# Wifi.net
KiCad netlist of a schematic drawn in Altium Designer
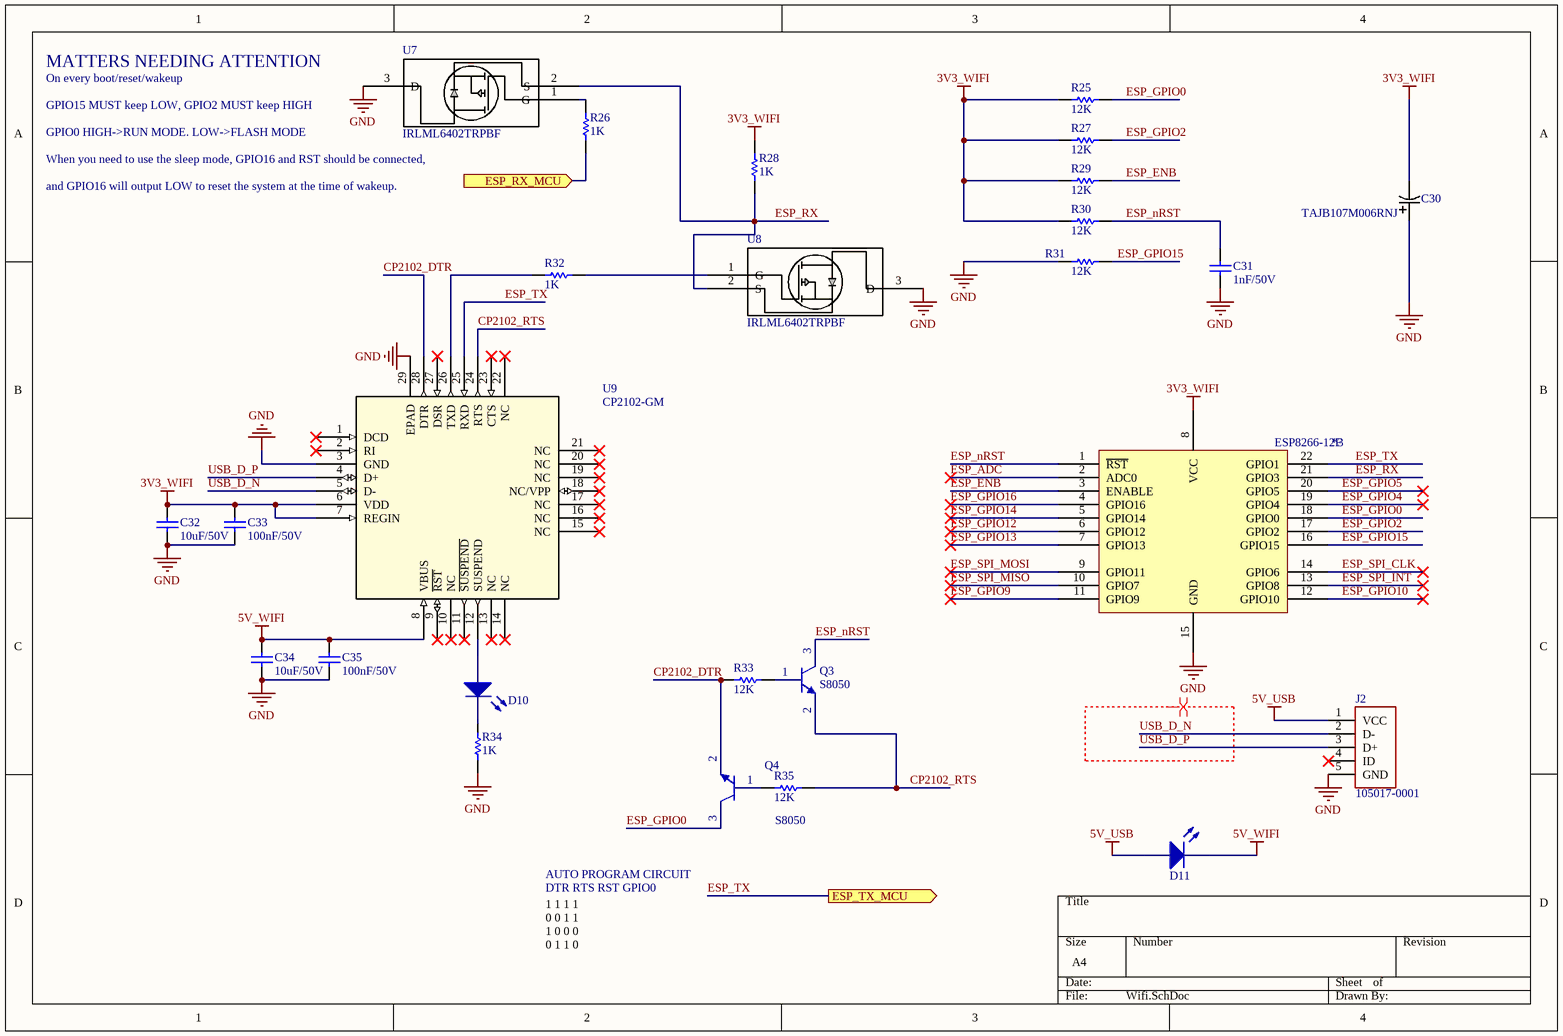
[diagram p0: Wifi.SchDoc]

(export (version "E")
  (design (tool "Eeschema 10.0.6"))
  (components
    (comp (ref "*3")
      (value "ESP8266-12F")
      (footprint "ESP8266")
      (libsource (lib "Schlib1") (part "ESP8266-12F"))
    )
    (comp (ref "C30")
      (value "TAJB107M006RNJ")
      (footprint "TAJB107M006RNJ")
      (fields (field (name "COPYRIGHT") "Copyright (C) 2018 Accelerated Designs. All rights reserved"))
      (libsource (lib "Integrated_Library") (part "TAJB107M006RNJ"))
    )
    (comp (ref "C31")
      (value "1nF/50V")
      (footprint "CAP-SM-0805")
      (description "CAP CER 1000PF 100V X7R 0805")
      (fields
        (field (name "MANUFACTURER") "Johanson Dielectrics Inc.")
        (field (name "MANUFACTURER PART NUMBER") "101X15W102MV4E")
      )
      (libsource (lib "Capacitor") (part "Cap-1nF-50V-0805"))
    )
    (comp (ref "C32")
      (value "10uF/50V")
      (footprint "CAP-SM-0805")
      (description "CAP CER 1000PF 100V X7R 0805")
      (fields
        (field (name "MANUFACTURER") "Johanson Dielectrics Inc.")
        (field (name "MANUFACTURER PART NUMBER") "101X15W102MV4E")
      )
      (libsource (lib "Capacitor") (part "Cap-1nF-50V-0805"))
    )
    (comp (ref "C33")
      (value "100nF/50V")
      (footprint "CAP-SM-0805")
      (description "CAP CER 1000PF 100V X7R 0805")
      (fields
        (field (name "MANUFACTURER") "Johanson Dielectrics Inc.")
        (field (name "MANUFACTURER PART NUMBER") "101X15W102MV4E")
      )
      (libsource (lib "Capacitor") (part "Cap-1nF-50V-0805"))
    )
    (comp (ref "C34")
      (value "10uF/50V")
      (footprint "CAP-SM-0805")
      (description "CAP CER 1000PF 100V X7R 0805")
      (fields
        (field (name "MANUFACTURER") "Johanson Dielectrics Inc.")
        (field (name "MANUFACTURER PART NUMBER") "101X15W102MV4E")
      )
      (libsource (lib "Capacitor") (part "Cap-1nF-50V-0805"))
    )
    (comp (ref "C35")
      (value "100nF/50V")
      (footprint "CAP-SM-0805")
      (description "CAP CER 1000PF 100V X7R 0805")
      (fields
        (field (name "MANUFACTURER") "Johanson Dielectrics Inc.")
        (field (name "MANUFACTURER PART NUMBER") "101X15W102MV4E")
      )
      (libsource (lib "Capacitor") (part "Cap-1nF-50V-0805"))
    )
    (comp (ref "D10") (value "LED") (footprint "LED_0603_Blue") (libsource (lib "PIF_C16_lib") (part "LED")))
    (comp (ref "D11") (value "LED") (footprint "LED_0603_Blue") (libsource (lib "PIF_C16_lib") (part "LED")))
    (comp (ref "J2")
      (value "105017-0001")
      (footprint "CONN_105017-0001")
      (description "No Description Available")
      (fields (field (name "COPYRIGHT") "Copyright (C) 2018 Accelerated Designs. All rights reserved"))
      (libsource (lib "Header-connector") (part "105017-0001"))
    )
    (comp (ref "Q3") (value "S8050") (footprint "SOT23_NEX") (libsource (lib "BJT") (part "S8050")))
    (comp (ref "Q4") (value "S8050") (footprint "SOT23_NEX") (libsource (lib "BJT") (part "S8050")))
    (comp (ref "R25")
      (value "12K")
      (footprint "Resistor:RES-SM-0805")
      (description "RES 0 OHM JUMPER 0805")
      (fields
        (field (name "MANUFACTURER") "Vishay Dale")
        (field (name "MANUFACTURER PART NUMBER") "WSL080500000ZEA9")
      )
      (libsource (lib "Resistor") (part "Res-0-0805"))
    )
    (comp (ref "R26")
      (value "1K")
      (footprint "Resistor:RES-SM-0805")
      (description "RES 470 OHM JUMPER 0805")
      (fields
        (field (name "MANUFACTURER") "YAG6006CT-ND")
        (field (name "MANUFACTURER PART NUMBER") "PE0805FRF7W0R047L")
      )
      (libsource (lib "Resistor") (part "Res-470-0805"))
    )
    (comp (ref "R27")
      (value "12K")
      (footprint "Resistor:RES-SM-0805")
      (description "RES 0 OHM JUMPER 0805")
      (fields
        (field (name "MANUFACTURER") "Vishay Dale")
        (field (name "MANUFACTURER PART NUMBER") "WSL080500000ZEA9")
      )
      (libsource (lib "Resistor") (part "Res-0-0805"))
    )
    (comp (ref "R28")
      (value "1K")
      (footprint "Resistor:RES-SM-0805")
      (description "RES 470 OHM JUMPER 0805")
      (fields
        (field (name "MANUFACTURER") "YAG6006CT-ND")
        (field (name "MANUFACTURER PART NUMBER") "PE0805FRF7W0R047L")
      )
      (libsource (lib "Resistor") (part "Res-470-0805"))
    )
    (comp (ref "R29")
      (value "12K")
      (footprint "Resistor:RES-SM-0805")
      (description "RES 0 OHM JUMPER 0805")
      (fields
        (field (name "MANUFACTURER") "Vishay Dale")
        (field (name "MANUFACTURER PART NUMBER") "WSL080500000ZEA9")
      )
      (libsource (lib "Resistor") (part "Res-0-0805"))
    )
    (comp (ref "R30")
      (value "12K")
      (footprint "Resistor:RES-SM-0805")
      (description "RES 0 OHM JUMPER 0805")
      (fields
        (field (name "MANUFACTURER") "Vishay Dale")
        (field (name "MANUFACTURER PART NUMBER") "WSL080500000ZEA9")
      )
      (libsource (lib "Resistor") (part "Res-0-0805"))
    )
    (comp (ref "R31")
      (value "12K")
      (footprint "Resistor:RES-SM-0805")
      (description "RES 0 OHM JUMPER 0805")
      (fields
        (field (name "MANUFACTURER") "Vishay Dale")
        (field (name "MANUFACTURER PART NUMBER") "WSL080500000ZEA9")
      )
      (libsource (lib "Resistor") (part "Res-0-0805"))
    )
    (comp (ref "R32")
      (value "1K")
      (footprint "Resistor:RES-SM-0805")
      (description "RES 470 OHM JUMPER 0805")
      (fields
        (field (name "MANUFACTURER") "YAG6006CT-ND")
        (field (name "MANUFACTURER PART NUMBER") "PE0805FRF7W0R047L")
      )
      (libsource (lib "Resistor") (part "Res-470-0805"))
    )
    (comp (ref "R33")
      (value "12K")
      (footprint "Resistor:RES-SM-0805")
      (description "RES 0 OHM JUMPER 0805")
      (fields
        (field (name "MANUFACTURER") "Vishay Dale")
        (field (name "MANUFACTURER PART NUMBER") "WSL080500000ZEA9")
      )
      (libsource (lib "Resistor") (part "Res-0-0805"))
    )
    (comp (ref "R34")
      (value "1K")
      (footprint "Resistor:RES-SM-0805")
      (description "RES 470 OHM JUMPER 0805")
      (fields
        (field (name "MANUFACTURER") "YAG6006CT-ND")
        (field (name "MANUFACTURER PART NUMBER") "PE0805FRF7W0R047L")
      )
      (libsource (lib "Resistor") (part "Res-470-0805"))
    )
    (comp (ref "R35")
      (value "12K")
      (footprint "Resistor:RES-SM-0805")
      (description "RES 0 OHM JUMPER 0805")
      (fields
        (field (name "MANUFACTURER") "Vishay Dale")
        (field (name "MANUFACTURER PART NUMBER") "WSL080500000ZEA9")
      )
      (libsource (lib "Resistor") (part "Res-0-0805"))
    )
    (comp (ref "U7")
      (value "IRLML6402TRPBF")
      (footprint "IRLML6402TRPBF")
      (description "No Description Available")
      (fields (field (name "COPYRIGHT") "Copyright (C) 2018 Accelerated Designs. All rights reserved"))
      (libsource (lib "Integrated_Library") (part "IRLML6402TRPBF"))
    )
    (comp (ref "U8")
      (value "IRLML6402TRPBF")
      (footprint "IRLML6402TRPBF")
      (description "No Description Available")
      (fields (field (name "COPYRIGHT") "Copyright (C) 2018 Accelerated Designs. All rights reserved"))
      (libsource (lib "Integrated_Library") (part "IRLML6402TRPBF"))
    )
    (comp (ref "U9")
      (value "CP2102-GM")
      (footprint "cp2102-gm")
      (fields (field (name "COPYRIGHT") "Copyright (C) 2018 Accelerated Designs. All rights reserved"))
      (libsource (lib "Schlib1") (part "CP2102-GM"))
    )
  )
  (nets
    (net (code "1") (name "/CP2102_DTR") (class "Default")
      (node (ref "Q4") (pin "2") (pinfunction "E_2") (pintype "passive"))
      (node (ref "R33") (pin "1") (pinfunction "1_1") (pintype "passive"))
      (node (ref "U9") (pin "28") (pinfunction "DTR_28") (pintype "output"))
    )
    (net (code "2") (name "/CP2102_RTS") (class "Default")
      (node (ref "Q3") (pin "2") (pinfunction "E_2") (pintype "passive"))
      (node (ref "R35") (pin "2") (pinfunction "2_2") (pintype "passive"))
      (node (ref "U9") (pin "24") (pinfunction "RTS_24") (pintype "output"))
    )
    (net (code "3") (name "/ESP_ADC") (class "Default")
      (node (ref "*3") (pin "2") (pinfunction "ADC0_2") (pintype "passive+no_connect"))
    )
    (net (code "4") (name "/ESP_ENB") (class "Default")
      (node (ref "*3") (pin "3") (pinfunction "ENABLE_3") (pintype "passive"))
      (node (ref "R29") (pin "2") (pinfunction "2_2") (pintype "passive"))
    )
    (net (code "5") (name "/ESP_GPIO0") (class "Default")
      (node (ref "*3") (pin "18") (pinfunction "GPIO0_18") (pintype "passive"))
      (node (ref "Q4") (pin "3") (pinfunction "C_3") (pintype "passive"))
      (node (ref "R25") (pin "2") (pinfunction "2_2") (pintype "passive"))
    )
    (net (code "6") (name "/ESP_GPIO2") (class "Default")
      (node (ref "*3") (pin "17") (pinfunction "GPIO2_17") (pintype "passive"))
      (node (ref "R27") (pin "2") (pinfunction "2_2") (pintype "passive"))
    )
    (net (code "7") (name "/ESP_GPIO4") (class "Default")
      (node (ref "*3") (pin "19") (pinfunction "GPIO4_19") (pintype "passive+no_connect"))
    )
    (net (code "8") (name "/ESP_GPIO5") (class "Default")
      (node (ref "*3") (pin "20") (pinfunction "GPIO5_20") (pintype "passive+no_connect"))
    )
    (net (code "9") (name "/ESP_GPIO9") (class "Default")
      (node (ref "*3") (pin "11") (pinfunction "GPIO9_11") (pintype "passive+no_connect"))
    )
    (net (code "10") (name "/ESP_GPIO10") (class "Default")
      (node (ref "*3") (pin "12") (pinfunction "GPIO10_12") (pintype "passive+no_connect"))
    )
    (net (code "11") (name "/ESP_GPIO12") (class "Default")
      (node (ref "*3") (pin "6") (pinfunction "GPIO12_6") (pintype "passive+no_connect"))
    )
    (net (code "12") (name "/ESP_GPIO13") (class "Default")
      (node (ref "*3") (pin "7") (pinfunction "GPIO13_7") (pintype "passive+no_connect"))
    )
    (net (code "13") (name "/ESP_GPIO14") (class "Default")
      (node (ref "*3") (pin "5") (pinfunction "GPIO14_5") (pintype "passive+no_connect"))
    )
    (net (code "14") (name "/ESP_GPIO15") (class "Default")
      (node (ref "*3") (pin "16") (pinfunction "GPIO15_16") (pintype "passive"))
      (node (ref "R31") (pin "2") (pinfunction "2_2") (pintype "passive"))
    )
    (net (code "15") (name "/ESP_GPIO16") (class "Default")
      (node (ref "*3") (pin "4") (pinfunction "GPIO16_4") (pintype "passive+no_connect"))
    )
    (net (code "16") (name "/ESP_RX") (class "Default")
      (node (ref "*3") (pin "21") (pinfunction "GPIO3_21") (pintype "passive"))
      (node (ref "R28") (pin "2") (pinfunction "2_2") (pintype "passive"))
      (node (ref "U7") (pin "2") (pinfunction "S_2") (pintype "passive"))
      (node (ref "U8") (pin "2") (pinfunction "S_2") (pintype "passive"))
    )
    (net (code "17") (name "/ESP_RX_MCU") (class "Default")
      (node (ref "R26") (pin "1") (pinfunction "1_1") (pintype "passive"))
    )
    (net (code "18") (name "/ESP_SPI_CLK") (class "Default")
      (node (ref "*3") (pin "14") (pinfunction "GPIO6_14") (pintype "passive+no_connect"))
    )
    (net (code "19") (name "/ESP_SPI_INT") (class "Default")
      (node (ref "*3") (pin "13") (pinfunction "GPIO8_13") (pintype "passive+no_connect"))
    )
    (net (code "20") (name "/ESP_SPI_MISO") (class "Default")
      (node (ref "*3") (pin "10") (pinfunction "GPIO7_10") (pintype "passive+no_connect"))
    )
    (net (code "21") (name "/ESP_SPI_MOSI") (class "Default")
      (node (ref "*3") (pin "9") (pinfunction "GPIO11_9") (pintype "passive+no_connect"))
    )
    (net (code "22") (name "/ESP_TX") (class "Default")
      (node (ref "*3") (pin "22") (pinfunction "GPIO1_22") (pintype "passive"))
      (node (ref "U9") (pin "25") (pinfunction "RXD_25") (pintype "input"))
    )
    (net (code "23") (name "/ESP_nRST") (class "Default")
      (node (ref "*3") (pin "1") (pinfunction "~{RST}_1") (pintype "passive"))
      (node (ref "C31") (pin "2") (pinfunction "2_2") (pintype "passive"))
      (node (ref "Q3") (pin "3") (pinfunction "C_3") (pintype "passive"))
      (node (ref "R30") (pin "2") (pinfunction "2_2") (pintype "passive"))
    )
    (net (code "24") (name "/USB_D_N") (class "Default")
      (node (ref "J2") (pin "2") (pinfunction "D-_2") (pintype "passive"))
      (node (ref "U9") (pin "5") (pinfunction "D-_5") (pintype "bidirectional"))
    )
    (net (code "25") (name "/USB_D_P") (class "Default")
      (node (ref "J2") (pin "3") (pinfunction "D+_3") (pintype "passive"))
      (node (ref "U9") (pin "4") (pinfunction "D+_4") (pintype "bidirectional"))
    )
    (net (code "26") (name "3V3_WIFI") (class "Default")
      (node (ref "*3") (pin "8") (pinfunction "VCC_8") (pintype "passive"))
      (node (ref "C30") (pin "2") (pinfunction "12_2") (pintype "passive"))
      (node (ref "C32") (pin "2") (pinfunction "2_2") (pintype "passive"))
      (node (ref "C33") (pin "2") (pinfunction "2_2") (pintype "passive"))
      (node (ref "R25") (pin "1") (pinfunction "1_1") (pintype "passive"))
      (node (ref "R27") (pin "1") (pinfunction "1_1") (pintype "passive"))
      (node (ref "R28") (pin "1") (pinfunction "1_1") (pintype "passive"))
      (node (ref "R29") (pin "1") (pinfunction "1_1") (pintype "passive"))
      (node (ref "R30") (pin "1") (pinfunction "1_1") (pintype "passive"))
      (node (ref "U9") (pin "6") (pinfunction "VDD_6") (pintype "power_in"))
      (node (ref "U9") (pin "7") (pinfunction "REGIN_7") (pintype "input"))
    )
    (net (code "27") (name "5V_USB") (class "Default")
      (node (ref "D11") (pin "1") (pinfunction "A_1") (pintype "passive"))
      (node (ref "J2") (pin "1") (pinfunction "VCC_1") (pintype "passive"))
    )
    (net (code "28") (name "5V_WIFI") (class "Default")
      (node (ref "C34") (pin "2") (pinfunction "2_2") (pintype "passive"))
      (node (ref "C35") (pin "2") (pinfunction "2_2") (pintype "passive"))
      (node (ref "D11") (pin "2") (pinfunction "K_2") (pintype "passive"))
      (node (ref "U9") (pin "8") (pinfunction "VBUS_8") (pintype "input"))
    )
    (net (code "29") (name "GND") (class "Default")
      (node (ref "*3") (pin "15") (pinfunction "GND_15") (pintype "passive"))
      (node (ref "C30") (pin "1") (pinfunction "11_1") (pintype "passive"))
      (node (ref "C31") (pin "1") (pinfunction "1_1") (pintype "passive"))
      (node (ref "C32") (pin "1") (pinfunction "1_1") (pintype "passive"))
      (node (ref "C33") (pin "1") (pinfunction "1_1") (pintype "passive"))
      (node (ref "C34") (pin "1") (pinfunction "1_1") (pintype "passive"))
      (node (ref "C35") (pin "1") (pinfunction "1_1") (pintype "passive"))
      (node (ref "J2") (pin "5") (pinfunction "GND_5") (pintype "passive"))
      (node (ref "R31") (pin "1") (pinfunction "1_1") (pintype "passive"))
      (node (ref "R34") (pin "1") (pinfunction "1_1") (pintype "passive"))
      (node (ref "U7") (pin "3") (pinfunction "D_3") (pintype "passive"))
      (node (ref "U8") (pin "3") (pinfunction "D_3") (pintype "passive"))
      (node (ref "U9") (pin "29") (pinfunction "EPAD_29") (pintype "passive"))
      (node (ref "U9") (pin "3") (pinfunction "GND_3") (pintype "power_in"))
    )
    (net (code "30") (name "Net-(D10-A)") (class "Default")
      (node (ref "D10") (pin "1") (pinfunction "A_1") (pintype "passive"))
      (node (ref "U9") (pin "12") (pinfunction "SUSPEND_12") (pintype "output"))
    )
    (net (code "31") (name "Net-(D10-K)") (class "Default")
      (node (ref "D10") (pin "2") (pinfunction "K_2") (pintype "passive"))
      (node (ref "R34") (pin "2") (pinfunction "2_2") (pintype "passive"))
    )
    (net (code "32") (name "Net-(Q3-B)") (class "Default")
      (node (ref "Q3") (pin "1") (pinfunction "B_1") (pintype "passive"))
      (node (ref "R33") (pin "2") (pinfunction "2_2") (pintype "passive"))
    )
    (net (code "33") (name "Net-(Q4-B)") (class "Default")
      (node (ref "Q4") (pin "1") (pinfunction "B_1") (pintype "passive"))
      (node (ref "R35") (pin "1") (pinfunction "1_1") (pintype "passive"))
    )
    (net (code "34") (name "Net-(U7-G)") (class "Default")
      (node (ref "R26") (pin "2") (pinfunction "2_2") (pintype "passive"))
      (node (ref "U7") (pin "1") (pinfunction "G_1") (pintype "passive"))
    )
    (net (code "35") (name "Net-(U8-G)") (class "Default")
      (node (ref "R32") (pin "1") (pinfunction "1_1") (pintype "passive"))
      (node (ref "U8") (pin "1") (pinfunction "G_1") (pintype "passive"))
    )
    (net (code "36") (name "Net-(U9-TXD)") (class "Default")
      (node (ref "R32") (pin "2") (pinfunction "2_2") (pintype "passive"))
      (node (ref "U9") (pin "26") (pinfunction "TXD_26") (pintype "output"))
    )
    (net (code "37") (name "unconnected-(J2-ID-Pad4)") (class "Default")
      (node (ref "J2") (pin "4") (pinfunction "ID_4") (pintype "passive+no_connect"))
    )
    (net (code "38") (name "unconnected-(U9-CTS-Pad23)") (class "Default")
      (node (ref "U9") (pin "23") (pinfunction "CTS_23") (pintype "input+no_connect"))
    )
    (net (code "39") (name "unconnected-(U9-DCD-Pad1)") (class "Default")
      (node (ref "U9") (pin "1") (pinfunction "DCD_1") (pintype "input+no_connect"))
    )
    (net (code "40") (name "unconnected-(U9-DSR-Pad27)") (class "Default")
      (node (ref "U9") (pin "27") (pinfunction "DSR_27") (pintype "input+no_connect"))
    )
    (net (code "41") (name "unconnected-(U9-NC-Pad10)") (class "Default")
      (node (ref "U9") (pin "10") (pinfunction "NC_10") (pintype "passive+no_connect"))
    )
    (net (code "42") (name "unconnected-(U9-NC-Pad13)") (class "Default")
      (node (ref "U9") (pin "13") (pinfunction "NC_13") (pintype "passive+no_connect"))
    )
    (net (code "43") (name "unconnected-(U9-NC-Pad14)") (class "Default")
      (node (ref "U9") (pin "14") (pinfunction "NC_14") (pintype "passive+no_connect"))
    )
    (net (code "44") (name "unconnected-(U9-NC-Pad15)") (class "Default")
      (node (ref "U9") (pin "15") (pinfunction "NC_15") (pintype "passive+no_connect"))
    )
    (net (code "45") (name "unconnected-(U9-NC-Pad16)") (class "Default")
      (node (ref "U9") (pin "16") (pinfunction "NC_16") (pintype "passive+no_connect"))
    )
    (net (code "46") (name "unconnected-(U9-NC-Pad17)") (class "Default")
      (node (ref "U9") (pin "17") (pinfunction "NC_17") (pintype "passive+no_connect"))
    )
    (net (code "47") (name "unconnected-(U9-NC-Pad19)") (class "Default")
      (node (ref "U9") (pin "19") (pinfunction "NC_19") (pintype "passive+no_connect"))
    )
    (net (code "48") (name "unconnected-(U9-NC-Pad20)") (class "Default")
      (node (ref "U9") (pin "20") (pinfunction "NC_20") (pintype "passive+no_connect"))
    )
    (net (code "49") (name "unconnected-(U9-NC-Pad21)") (class "Default")
      (node (ref "U9") (pin "21") (pinfunction "NC_21") (pintype "passive+no_connect"))
    )
    (net (code "50") (name "unconnected-(U9-NC-Pad22)") (class "Default")
      (node (ref "U9") (pin "22") (pinfunction "NC_22") (pintype "passive+no_connect"))
    )
    (net (code "51") (name "unconnected-(U9-NC{slash}VPP-Pad18)") (class "Default")
      (node (ref "U9") (pin "18") (pinfunction "NC/VPP_18") (pintype "bidirectional+no_connect"))
    )
    (net (code "52") (name "unconnected-(U9-RI-Pad2)") (class "Default")
      (node (ref "U9") (pin "2") (pinfunction "RI_2") (pintype "input+no_connect"))
    )
    (net (code "53") (name "unconnected-(U9-~{RST}-Pad9)") (class "Default")
      (node (ref "U9") (pin "9") (pinfunction "~{RST}_9") (pintype "bidirectional+no_connect"))
    )
    (net (code "54") (name "unconnected-(U9-~{SUSPEND}-Pad11)") (class "Default")
      (node (ref "U9") (pin "11") (pinfunction "~{SUSPEND}_11") (pintype "output+no_connect"))
    )
  )
)
